# cob.net
KiCad netlist of a schematic drawn in EAGLE
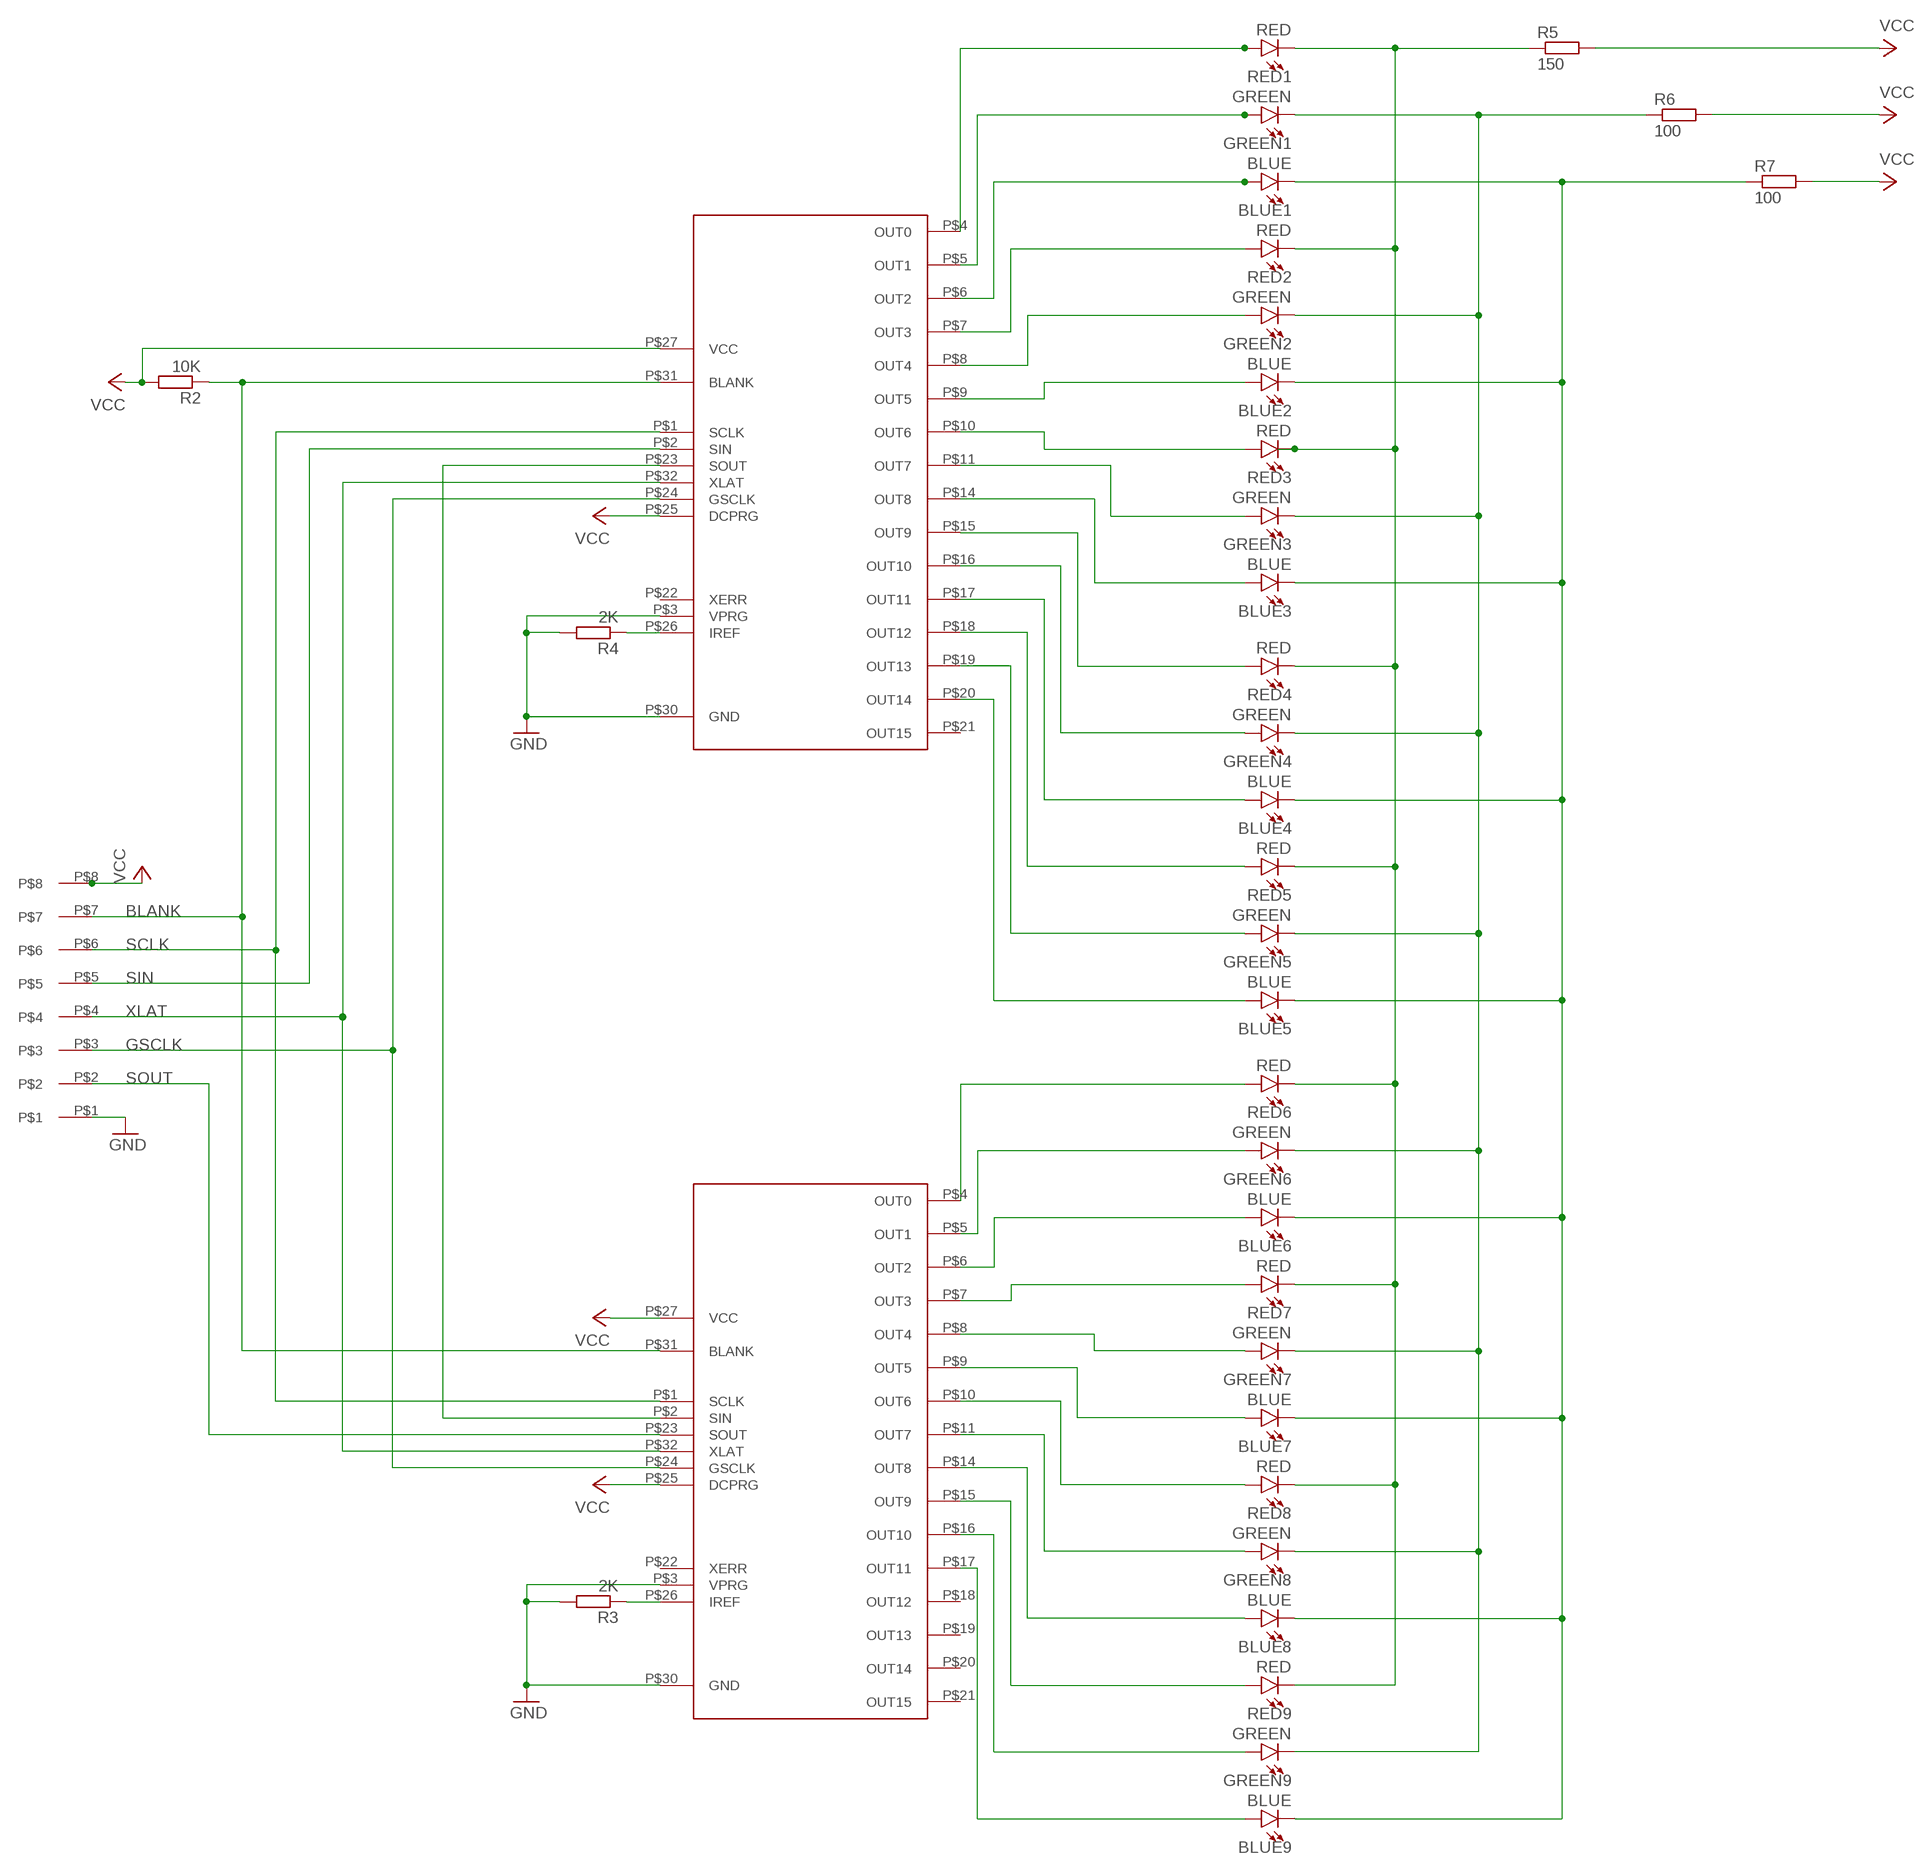
[diagram p0: schematic, sheet 1]

(export (version "E")
  (design (tool "Eeschema 10.0.6"))
  (components
    (comp (ref "BLUE1")
      (value "BLUE")
      (footprint "eagle-import:LED-0603")
      (libsource (lib "eagle-import") (part "LED-BLUE0603"))
    )
    (comp (ref "BLUE2")
      (value "BLUE")
      (footprint "eagle-import:LED-0603")
      (libsource (lib "eagle-import") (part "LED-BLUE0603"))
    )
    (comp (ref "BLUE3")
      (value "BLUE")
      (footprint "eagle-import:LED-0603")
      (libsource (lib "eagle-import") (part "LED-BLUE0603"))
    )
    (comp (ref "BLUE4")
      (value "BLUE")
      (footprint "eagle-import:LED-0603")
      (libsource (lib "eagle-import") (part "LED-BLUE0603"))
    )
    (comp (ref "BLUE5")
      (value "BLUE")
      (footprint "eagle-import:LED-0603")
      (libsource (lib "eagle-import") (part "LED-BLUE0603"))
    )
    (comp (ref "BLUE6")
      (value "BLUE")
      (footprint "eagle-import:LED-0603")
      (libsource (lib "eagle-import") (part "LED-BLUE0603"))
    )
    (comp (ref "BLUE7")
      (value "BLUE")
      (footprint "eagle-import:LED-0603")
      (libsource (lib "eagle-import") (part "LED-BLUE0603"))
    )
    (comp (ref "BLUE8")
      (value "BLUE")
      (footprint "eagle-import:LED-0603")
      (libsource (lib "eagle-import") (part "LED-BLUE0603"))
    )
    (comp (ref "BLUE9")
      (value "BLUE")
      (footprint "eagle-import:LED-0603")
      (libsource (lib "eagle-import") (part "LED-BLUE0603"))
    )
    (comp (ref "GREEN1")
      (value "GREEN")
      (footprint "eagle-import:LED-0603")
      (libsource (lib "eagle-import") (part "LED-GREEN0603"))
    )
    (comp (ref "GREEN2")
      (value "GREEN")
      (footprint "eagle-import:LED-0603")
      (libsource (lib "eagle-import") (part "LED-GREEN0603"))
    )
    (comp (ref "GREEN3")
      (value "GREEN")
      (footprint "eagle-import:LED-0603")
      (libsource (lib "eagle-import") (part "LED-GREEN0603"))
    )
    (comp (ref "GREEN4")
      (value "GREEN")
      (footprint "eagle-import:LED-0603")
      (libsource (lib "eagle-import") (part "LED-GREEN0603"))
    )
    (comp (ref "GREEN5")
      (value "GREEN")
      (footprint "eagle-import:LED-0603")
      (libsource (lib "eagle-import") (part "LED-GREEN0603"))
    )
    (comp (ref "GREEN6")
      (value "GREEN")
      (footprint "eagle-import:LED-0603")
      (libsource (lib "eagle-import") (part "LED-GREEN0603"))
    )
    (comp (ref "GREEN7")
      (value "GREEN")
      (footprint "eagle-import:LED-0603")
      (libsource (lib "eagle-import") (part "LED-GREEN0603"))
    )
    (comp (ref "GREEN8")
      (value "GREEN")
      (footprint "eagle-import:LED-0603")
      (libsource (lib "eagle-import") (part "LED-GREEN0603"))
    )
    (comp (ref "GREEN9")
      (value "GREEN")
      (footprint "eagle-import:LED-0603")
      (libsource (lib "eagle-import") (part "LED-GREEN0603"))
    )
    (comp (ref "R2")
      (value "10K")
      (footprint "eagle-import:R0402")
      (libsource (lib "eagle-import") (part "R-EU_R0402"))
    )
    (comp (ref "R3")
      (value "2K")
      (footprint "eagle-import:R0402")
      (libsource (lib "eagle-import") (part "R-EU_R0402"))
    )
    (comp (ref "R4")
      (value "2K")
      (footprint "eagle-import:R0402")
      (libsource (lib "eagle-import") (part "R-EU_R0402"))
    )
    (comp (ref "R5")
      (value "150")
      (footprint "eagle-import:R1206")
      (libsource (lib "eagle-import") (part "R-EU_R1206"))
    )
    (comp (ref "R6")
      (value "100")
      (footprint "eagle-import:R1206")
      (libsource (lib "eagle-import") (part "R-EU_R1206"))
    )
    (comp (ref "R7")
      (value "100")
      (footprint "eagle-import:R1206")
      (libsource (lib "eagle-import") (part "R-EU_R1206"))
    )
    (comp (ref "RED1")
      (value "RED")
      (footprint "eagle-import:LED-0603")
      (libsource (lib "eagle-import") (part "LED-RED0603"))
    )
    (comp (ref "RED2")
      (value "RED")
      (footprint "eagle-import:LED-0603")
      (libsource (lib "eagle-import") (part "LED-RED0603"))
    )
    (comp (ref "RED3")
      (value "RED")
      (footprint "eagle-import:LED-0603")
      (libsource (lib "eagle-import") (part "LED-RED0603"))
    )
    (comp (ref "RED4")
      (value "RED")
      (footprint "eagle-import:LED-0603")
      (libsource (lib "eagle-import") (part "LED-RED0603"))
    )
    (comp (ref "RED5")
      (value "RED")
      (footprint "eagle-import:LED-0603")
      (libsource (lib "eagle-import") (part "LED-RED0603"))
    )
    (comp (ref "RED6")
      (value "RED")
      (footprint "eagle-import:LED-0603")
      (libsource (lib "eagle-import") (part "LED-RED0603"))
    )
    (comp (ref "RED7")
      (value "RED")
      (footprint "eagle-import:LED-0603")
      (libsource (lib "eagle-import") (part "LED-RED0603"))
    )
    (comp (ref "RED8")
      (value "RED")
      (footprint "eagle-import:LED-0603")
      (libsource (lib "eagle-import") (part "LED-RED0603"))
    )
    (comp (ref "RED9")
      (value "RED")
      (footprint "eagle-import:LED-0603")
      (libsource (lib "eagle-import") (part "LED-RED0603"))
    )
    (comp (ref "U$1")
      (value "TLC5940")
      (footprint "eagle-import:RHB")
      (libsource (lib "eagle-import") (part "TLC5940"))
    )
    (comp (ref "U$2")
      (value "TLC5940")
      (footprint "eagle-import:RHB")
      (libsource (lib "eagle-import") (part "TLC5940"))
    )
    (comp (ref "U$3")
      (value "8PIN")
      (footprint "eagle-import:8PIN")
      (libsource (lib "eagle-import") (part "8PIN"))
    )
  )
  (nets
    (net (code "1") (name "/BLANK") (class "Default")
      (node (ref "R2") (pin "1") (pinfunction "1_1") (pintype "passive"))
      (node (ref "U$1") (pin "P$31") (pinfunction "BLANK_P$31") (pintype "bidirectional"))
      (node (ref "U$2") (pin "P$31") (pinfunction "BLANK_P$31") (pintype "bidirectional"))
      (node (ref "U$3") (pin "P$7") (pinfunction "P$7_P$7") (pintype "bidirectional"))
    )
    (net (code "2") (name "/GSCLK") (class "Default")
      (node (ref "U$1") (pin "P$24") (pinfunction "GSCLK_P$24") (pintype "bidirectional"))
      (node (ref "U$2") (pin "P$24") (pinfunction "GSCLK_P$24") (pintype "bidirectional"))
      (node (ref "U$3") (pin "P$3") (pinfunction "P$3_P$3") (pintype "bidirectional"))
    )
    (net (code "3") (name "/SCLK") (class "Default")
      (node (ref "U$1") (pin "P$1") (pinfunction "SCLK_P$1") (pintype "bidirectional"))
      (node (ref "U$2") (pin "P$1") (pinfunction "SCLK_P$1") (pintype "bidirectional"))
      (node (ref "U$3") (pin "P$6") (pinfunction "P$6_P$6") (pintype "bidirectional"))
    )
    (net (code "4") (name "/SIN") (class "Default")
      (node (ref "U$1") (pin "P$2") (pinfunction "SIN_P$2") (pintype "bidirectional"))
      (node (ref "U$3") (pin "P$5") (pinfunction "P$5_P$5") (pintype "bidirectional"))
    )
    (net (code "5") (name "/SOUT") (class "Default")
      (node (ref "U$2") (pin "P$23") (pinfunction "SOUT_P$23") (pintype "bidirectional"))
      (node (ref "U$3") (pin "P$2") (pinfunction "P$2_P$2") (pintype "bidirectional"))
    )
    (net (code "6") (name "/XLAT") (class "Default")
      (node (ref "U$1") (pin "P$32") (pinfunction "XLAT_P$32") (pintype "bidirectional"))
      (node (ref "U$2") (pin "P$32") (pinfunction "XLAT_P$32") (pintype "bidirectional"))
      (node (ref "U$3") (pin "P$4") (pinfunction "P$4_P$4") (pintype "bidirectional"))
    )
    (net (code "7") (name "GND") (class "Default")
      (node (ref "R3") (pin "2") (pinfunction "2_2") (pintype "passive"))
      (node (ref "R4") (pin "2") (pinfunction "2_2") (pintype "passive"))
      (node (ref "U$1") (pin "P$3") (pinfunction "VPRG_P$3") (pintype "bidirectional"))
      (node (ref "U$1") (pin "P$30") (pinfunction "GND_P$30") (pintype "bidirectional"))
      (node (ref "U$2") (pin "P$3") (pinfunction "VPRG_P$3") (pintype "bidirectional"))
      (node (ref "U$2") (pin "P$30") (pinfunction "GND_P$30") (pintype "bidirectional"))
      (node (ref "U$3") (pin "P$1") (pinfunction "P$1_P$1") (pintype "bidirectional"))
    )
    (net (code "8") (name "Net-(BLUE1-PadC)") (class "Default")
      (node (ref "BLUE1") (pin "C") (pinfunction "C_C") (pintype "passive"))
      (node (ref "BLUE2") (pin "C") (pinfunction "C_C") (pintype "passive"))
      (node (ref "BLUE3") (pin "C") (pinfunction "C_C") (pintype "passive"))
      (node (ref "BLUE4") (pin "C") (pinfunction "C_C") (pintype "passive"))
      (node (ref "BLUE5") (pin "C") (pinfunction "C_C") (pintype "passive"))
      (node (ref "BLUE6") (pin "C") (pinfunction "C_C") (pintype "passive"))
      (node (ref "BLUE7") (pin "C") (pinfunction "C_C") (pintype "passive"))
      (node (ref "BLUE8") (pin "C") (pinfunction "C_C") (pintype "passive"))
      (node (ref "BLUE9") (pin "C") (pinfunction "C_C") (pintype "passive"))
      (node (ref "R7") (pin "1") (pinfunction "1_1") (pintype "passive"))
    )
    (net (code "9") (name "Net-(GREEN1-PadC)") (class "Default")
      (node (ref "GREEN1") (pin "C") (pinfunction "C_C") (pintype "passive"))
      (node (ref "GREEN2") (pin "C") (pinfunction "C_C") (pintype "passive"))
      (node (ref "GREEN3") (pin "C") (pinfunction "C_C") (pintype "passive"))
      (node (ref "GREEN4") (pin "C") (pinfunction "C_C") (pintype "passive"))
      (node (ref "GREEN5") (pin "C") (pinfunction "C_C") (pintype "passive"))
      (node (ref "GREEN6") (pin "C") (pinfunction "C_C") (pintype "passive"))
      (node (ref "GREEN7") (pin "C") (pinfunction "C_C") (pintype "passive"))
      (node (ref "GREEN8") (pin "C") (pinfunction "C_C") (pintype "passive"))
      (node (ref "GREEN9") (pin "C") (pinfunction "C_C") (pintype "passive"))
      (node (ref "R6") (pin "1") (pinfunction "1_1") (pintype "passive"))
    )
    (net (code "10") (name "Net-(R5-Pad1)") (class "Default")
      (node (ref "R5") (pin "1") (pinfunction "1_1") (pintype "passive"))
      (node (ref "RED1") (pin "C") (pinfunction "C_C") (pintype "passive"))
      (node (ref "RED2") (pin "C") (pinfunction "C_C") (pintype "passive"))
      (node (ref "RED3") (pin "C") (pinfunction "C_C") (pintype "passive"))
      (node (ref "RED4") (pin "C") (pinfunction "C_C") (pintype "passive"))
      (node (ref "RED5") (pin "C") (pinfunction "C_C") (pintype "passive"))
      (node (ref "RED6") (pin "C") (pinfunction "C_C") (pintype "passive"))
      (node (ref "RED7") (pin "C") (pinfunction "C_C") (pintype "passive"))
      (node (ref "RED8") (pin "C") (pinfunction "C_C") (pintype "passive"))
      (node (ref "RED9") (pin "C") (pinfunction "C_C") (pintype "passive"))
    )
    (net (code "11") (name "Net-(U$1-IREF)") (class "Default")
      (node (ref "R4") (pin "1") (pinfunction "1_1") (pintype "passive"))
      (node (ref "U$1") (pin "P$26") (pinfunction "IREF_P$26") (pintype "bidirectional"))
    )
    (net (code "12") (name "Net-(U$1-OUT0)") (class "Default")
      (node (ref "RED1") (pin "A") (pinfunction "A_A") (pintype "passive"))
      (node (ref "U$1") (pin "P$4") (pinfunction "OUT0_P$4") (pintype "bidirectional"))
    )
    (net (code "13") (name "Net-(U$1-OUT1)") (class "Default")
      (node (ref "GREEN1") (pin "A") (pinfunction "A_A") (pintype "passive"))
      (node (ref "U$1") (pin "P$5") (pinfunction "OUT1_P$5") (pintype "bidirectional"))
    )
    (net (code "14") (name "Net-(U$1-OUT2)") (class "Default")
      (node (ref "BLUE1") (pin "A") (pinfunction "A_A") (pintype "passive"))
      (node (ref "U$1") (pin "P$6") (pinfunction "OUT2_P$6") (pintype "bidirectional"))
    )
    (net (code "15") (name "Net-(U$1-OUT3)") (class "Default")
      (node (ref "RED2") (pin "A") (pinfunction "A_A") (pintype "passive"))
      (node (ref "U$1") (pin "P$7") (pinfunction "OUT3_P$7") (pintype "bidirectional"))
    )
    (net (code "16") (name "Net-(U$1-OUT4)") (class "Default")
      (node (ref "GREEN2") (pin "A") (pinfunction "A_A") (pintype "passive"))
      (node (ref "U$1") (pin "P$8") (pinfunction "OUT4_P$8") (pintype "bidirectional"))
    )
    (net (code "17") (name "Net-(U$1-OUT5)") (class "Default")
      (node (ref "BLUE2") (pin "A") (pinfunction "A_A") (pintype "passive"))
      (node (ref "U$1") (pin "P$9") (pinfunction "OUT5_P$9") (pintype "bidirectional"))
    )
    (net (code "18") (name "Net-(U$1-OUT6)") (class "Default")
      (node (ref "RED3") (pin "A") (pinfunction "A_A") (pintype "passive"))
      (node (ref "U$1") (pin "P$10") (pinfunction "OUT6_P$10") (pintype "bidirectional"))
    )
    (net (code "19") (name "Net-(U$1-OUT7)") (class "Default")
      (node (ref "GREEN3") (pin "A") (pinfunction "A_A") (pintype "passive"))
      (node (ref "U$1") (pin "P$11") (pinfunction "OUT7_P$11") (pintype "bidirectional"))
    )
    (net (code "20") (name "Net-(U$1-OUT8)") (class "Default")
      (node (ref "BLUE3") (pin "A") (pinfunction "A_A") (pintype "passive"))
      (node (ref "U$1") (pin "P$14") (pinfunction "OUT8_P$14") (pintype "bidirectional"))
    )
    (net (code "21") (name "Net-(U$1-OUT9)") (class "Default")
      (node (ref "RED4") (pin "A") (pinfunction "A_A") (pintype "passive"))
      (node (ref "U$1") (pin "P$15") (pinfunction "OUT9_P$15") (pintype "bidirectional"))
    )
    (net (code "22") (name "Net-(U$1-OUT10)") (class "Default")
      (node (ref "GREEN4") (pin "A") (pinfunction "A_A") (pintype "passive"))
      (node (ref "U$1") (pin "P$16") (pinfunction "OUT10_P$16") (pintype "bidirectional"))
    )
    (net (code "23") (name "Net-(U$1-OUT11)") (class "Default")
      (node (ref "BLUE4") (pin "A") (pinfunction "A_A") (pintype "passive"))
      (node (ref "U$1") (pin "P$17") (pinfunction "OUT11_P$17") (pintype "bidirectional"))
    )
    (net (code "24") (name "Net-(U$1-OUT12)") (class "Default")
      (node (ref "RED5") (pin "A") (pinfunction "A_A") (pintype "passive"))
      (node (ref "U$1") (pin "P$18") (pinfunction "OUT12_P$18") (pintype "bidirectional"))
    )
    (net (code "25") (name "Net-(U$1-OUT13)") (class "Default")
      (node (ref "GREEN5") (pin "A") (pinfunction "A_A") (pintype "passive"))
      (node (ref "U$1") (pin "P$19") (pinfunction "OUT13_P$19") (pintype "bidirectional"))
    )
    (net (code "26") (name "Net-(U$1-OUT14)") (class "Default")
      (node (ref "BLUE5") (pin "A") (pinfunction "A_A") (pintype "passive"))
      (node (ref "U$1") (pin "P$20") (pinfunction "OUT14_P$20") (pintype "bidirectional"))
    )
    (net (code "27") (name "Net-(U$1-SOUT)") (class "Default")
      (node (ref "U$1") (pin "P$23") (pinfunction "SOUT_P$23") (pintype "bidirectional"))
      (node (ref "U$2") (pin "P$2") (pinfunction "SIN_P$2") (pintype "bidirectional"))
    )
    (net (code "28") (name "Net-(U$2-IREF)") (class "Default")
      (node (ref "R3") (pin "1") (pinfunction "1_1") (pintype "passive"))
      (node (ref "U$2") (pin "P$26") (pinfunction "IREF_P$26") (pintype "bidirectional"))
    )
    (net (code "29") (name "Net-(U$2-OUT0)") (class "Default")
      (node (ref "RED6") (pin "A") (pinfunction "A_A") (pintype "passive"))
      (node (ref "U$2") (pin "P$4") (pinfunction "OUT0_P$4") (pintype "bidirectional"))
    )
    (net (code "30") (name "Net-(U$2-OUT1)") (class "Default")
      (node (ref "GREEN6") (pin "A") (pinfunction "A_A") (pintype "passive"))
      (node (ref "U$2") (pin "P$5") (pinfunction "OUT1_P$5") (pintype "bidirectional"))
    )
    (net (code "31") (name "Net-(U$2-OUT2)") (class "Default")
      (node (ref "BLUE6") (pin "A") (pinfunction "A_A") (pintype "passive"))
      (node (ref "U$2") (pin "P$6") (pinfunction "OUT2_P$6") (pintype "bidirectional"))
    )
    (net (code "32") (name "Net-(U$2-OUT3)") (class "Default")
      (node (ref "RED7") (pin "A") (pinfunction "A_A") (pintype "passive"))
      (node (ref "U$2") (pin "P$7") (pinfunction "OUT3_P$7") (pintype "bidirectional"))
    )
    (net (code "33") (name "Net-(U$2-OUT4)") (class "Default")
      (node (ref "GREEN7") (pin "A") (pinfunction "A_A") (pintype "passive"))
      (node (ref "U$2") (pin "P$8") (pinfunction "OUT4_P$8") (pintype "bidirectional"))
    )
    (net (code "34") (name "Net-(U$2-OUT5)") (class "Default")
      (node (ref "BLUE7") (pin "A") (pinfunction "A_A") (pintype "passive"))
      (node (ref "U$2") (pin "P$9") (pinfunction "OUT5_P$9") (pintype "bidirectional"))
    )
    (net (code "35") (name "Net-(U$2-OUT6)") (class "Default")
      (node (ref "RED8") (pin "A") (pinfunction "A_A") (pintype "passive"))
      (node (ref "U$2") (pin "P$10") (pinfunction "OUT6_P$10") (pintype "bidirectional"))
    )
    (net (code "36") (name "Net-(U$2-OUT7)") (class "Default")
      (node (ref "GREEN8") (pin "A") (pinfunction "A_A") (pintype "passive"))
      (node (ref "U$2") (pin "P$11") (pinfunction "OUT7_P$11") (pintype "bidirectional"))
    )
    (net (code "37") (name "Net-(U$2-OUT8)") (class "Default")
      (node (ref "BLUE8") (pin "A") (pinfunction "A_A") (pintype "passive"))
      (node (ref "U$2") (pin "P$14") (pinfunction "OUT8_P$14") (pintype "bidirectional"))
    )
    (net (code "38") (name "Net-(U$2-OUT9)") (class "Default")
      (node (ref "RED9") (pin "A") (pinfunction "A_A") (pintype "passive"))
      (node (ref "U$2") (pin "P$15") (pinfunction "OUT9_P$15") (pintype "bidirectional"))
    )
    (net (code "39") (name "Net-(U$2-OUT10)") (class "Default")
      (node (ref "GREEN9") (pin "A") (pinfunction "A_A") (pintype "passive"))
      (node (ref "U$2") (pin "P$16") (pinfunction "OUT10_P$16") (pintype "bidirectional"))
    )
    (net (code "40") (name "Net-(U$2-OUT11)") (class "Default")
      (node (ref "BLUE9") (pin "A") (pinfunction "A_A") (pintype "passive"))
      (node (ref "U$2") (pin "P$17") (pinfunction "OUT11_P$17") (pintype "bidirectional"))
    )
    (net (code "41") (name "VCC") (class "Default")
      (node (ref "R2") (pin "2") (pinfunction "2_2") (pintype "passive"))
      (node (ref "R5") (pin "2") (pinfunction "2_2") (pintype "passive"))
      (node (ref "R6") (pin "2") (pinfunction "2_2") (pintype "passive"))
      (node (ref "R7") (pin "2") (pinfunction "2_2") (pintype "passive"))
      (node (ref "U$1") (pin "P$25") (pinfunction "DCPRG_P$25") (pintype "bidirectional"))
      (node (ref "U$1") (pin "P$27") (pinfunction "VCC_P$27") (pintype "bidirectional"))
      (node (ref "U$2") (pin "P$25") (pinfunction "DCPRG_P$25") (pintype "bidirectional"))
      (node (ref "U$2") (pin "P$27") (pinfunction "VCC_P$27") (pintype "bidirectional"))
      (node (ref "U$3") (pin "P$8") (pinfunction "P$8_P$8") (pintype "bidirectional"))
    )
    (net (code "42") (name "unconnected-(U$1-OUT15-PadP$21)") (class "Default")
      (node (ref "U$1") (pin "P$21") (pinfunction "OUT15_P$21") (pintype "bidirectional"))
    )
    (net (code "43") (name "unconnected-(U$1-XERR-PadP$22)") (class "Default")
      (node (ref "U$1") (pin "P$22") (pinfunction "XERR_P$22") (pintype "bidirectional"))
    )
    (net (code "44") (name "unconnected-(U$2-OUT12-PadP$18)") (class "Default")
      (node (ref "U$2") (pin "P$18") (pinfunction "OUT12_P$18") (pintype "bidirectional"))
    )
    (net (code "45") (name "unconnected-(U$2-OUT13-PadP$19)") (class "Default")
      (node (ref "U$2") (pin "P$19") (pinfunction "OUT13_P$19") (pintype "bidirectional"))
    )
    (net (code "46") (name "unconnected-(U$2-OUT14-PadP$20)") (class "Default")
      (node (ref "U$2") (pin "P$20") (pinfunction "OUT14_P$20") (pintype "bidirectional"))
    )
    (net (code "47") (name "unconnected-(U$2-OUT15-PadP$21)") (class "Default")
      (node (ref "U$2") (pin "P$21") (pinfunction "OUT15_P$21") (pintype "bidirectional"))
    )
    (net (code "48") (name "unconnected-(U$2-XERR-PadP$22)") (class "Default")
      (node (ref "U$2") (pin "P$22") (pinfunction "XERR_P$22") (pintype "bidirectional"))
    )
  )
)
